# usb-geiger.net
KiCad netlist of a schematic drawn in EAGLE
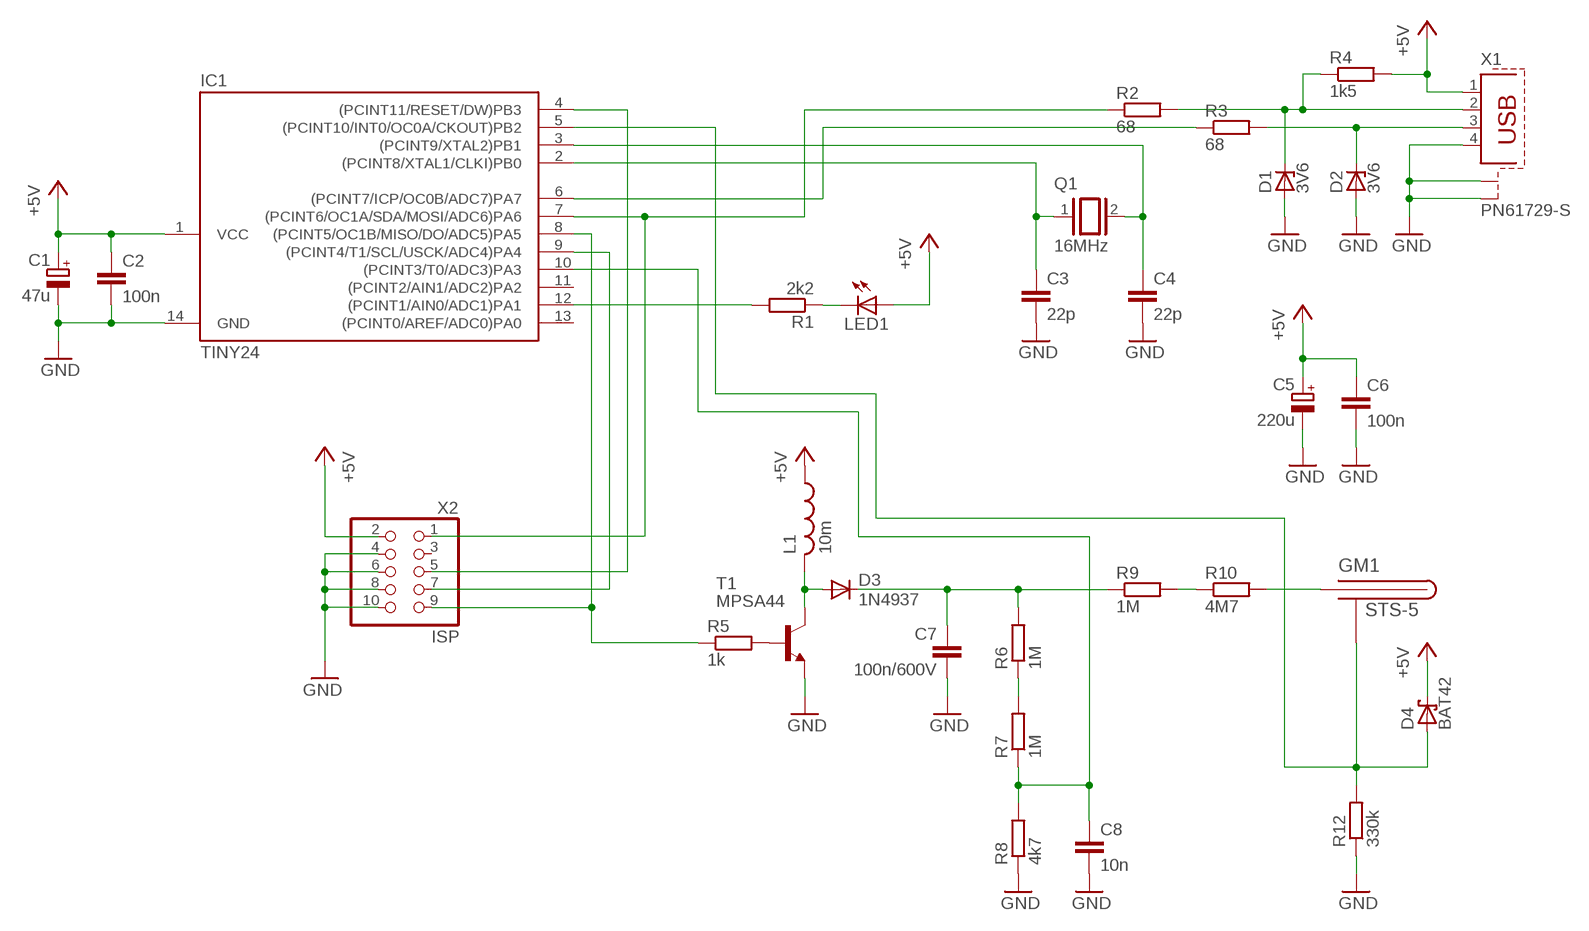
[diagram p0: schematic, sheet 1]

(export (version "E")
  (design (tool "Eeschema 10.0.6"))
  (components
    (comp (ref "C1")
      (value "47u")
      (footprint "eagle-import:E2,5-6")
      (libsource (lib "eagle-import") (part "CPOL-EUE2.5-6"))
    )
    (comp (ref "C2")
      (value "100n")
      (footprint "eagle-import:C050-025X075")
      (libsource (lib "eagle-import") (part "C-EU050-025X075"))
    )
    (comp (ref "C3")
      (value "22p")
      (footprint "eagle-import:C025-025X050")
      (libsource (lib "eagle-import") (part "C-EU025-025X050"))
    )
    (comp (ref "C4")
      (value "22p")
      (footprint "eagle-import:C025-025X050")
      (libsource (lib "eagle-import") (part "C-EU025-025X050"))
    )
    (comp (ref "C5")
      (value "220u")
      (footprint "eagle-import:E5-10,5")
      (libsource (lib "eagle-import") (part "CPOL-EUE5-10.5"))
    )
    (comp (ref "C6")
      (value "100n")
      (footprint "eagle-import:C050-025X075")
      (libsource (lib "eagle-import") (part "C-EU050-025X075"))
    )
    (comp (ref "C7")
      (value "100n/600V")
      (footprint "eagle-import:C225-113X268")
      (libsource (lib "eagle-import") (part "C-EU225-113X268"))
    )
    (comp (ref "C8")
      (value "10n")
      (footprint "eagle-import:C050-025X075")
      (libsource (lib "eagle-import") (part "C-EU050-025X075"))
    )
    (comp (ref "D1")
      (value "3V6")
      (footprint "eagle-import:DO34Z7")
      (libsource (lib "eagle-import") (part "ZENER-DIODEDO34-7"))
    )
    (comp (ref "D2")
      (value "3V6")
      (footprint "eagle-import:DO34Z7")
      (libsource (lib "eagle-import") (part "ZENER-DIODEDO34-7"))
    )
    (comp (ref "D3")
      (value "1N4937")
      (footprint "eagle-import:DO41-10")
      (libsource (lib "eagle-import") (part "1N4933"))
    )
    (comp (ref "D4")
      (value "BAT42")
      (footprint "eagle-import:DO35-10")
      (libsource (lib "eagle-import") (part "BAT42"))
    )
    (comp (ref "GM1")
      (value "STS-5")
      (footprint "eagle-import:STS-5")
      (libsource (lib "eagle-import") (part "STS-5"))
    )
    (comp (ref "IC1")
      (value "TINY24")
      (footprint "eagle-import:DIL14")
      (libsource (lib "eagle-import") (part "TINY24/44/84-PU"))
    )
    (comp (ref "L1")
      (value "10m")
      (footprint "eagle-import:0207_5V")
      (libsource (lib "eagle-import") (part "L-US0207/5V"))
    )
    (comp (ref "LED1")
      (value "LED3MM")
      (footprint "eagle-import:LED3MM")
      (libsource (lib "eagle-import") (part "LED3MM"))
    )
    (comp (ref "Q1")
      (value "16MHz")
      (footprint "eagle-import:QS")
      (libsource (lib "eagle-import") (part "XTAL/S"))
    )
    (comp (ref "R1")
      (value "2k2")
      (footprint "eagle-import:0207_10")
      (libsource (lib "eagle-import") (part "R-EU_0207/10"))
    )
    (comp (ref "R2")
      (value "68")
      (footprint "eagle-import:0207_10")
      (libsource (lib "eagle-import") (part "R-EU_0207/10"))
    )
    (comp (ref "R3")
      (value "68")
      (footprint "eagle-import:0207_10")
      (libsource (lib "eagle-import") (part "R-EU_0207/10"))
    )
    (comp (ref "R4")
      (value "1k5")
      (footprint "eagle-import:0207_10")
      (libsource (lib "eagle-import") (part "R-EU_0207/10"))
    )
    (comp (ref "R5")
      (value "1k")
      (footprint "eagle-import:0207_10")
      (libsource (lib "eagle-import") (part "R-EU_0207/10"))
    )
    (comp (ref "R6")
      (value "1M")
      (footprint "eagle-import:0207_10")
      (libsource (lib "eagle-import") (part "R-EU_0207/10"))
    )
    (comp (ref "R7")
      (value "1M")
      (footprint "eagle-import:0207_10")
      (libsource (lib "eagle-import") (part "R-EU_0207/10"))
    )
    (comp (ref "R8")
      (value "4k7")
      (footprint "eagle-import:0207_10")
      (libsource (lib "eagle-import") (part "R-EU_0207/10"))
    )
    (comp (ref "R9")
      (value "1M")
      (footprint "eagle-import:0207_10")
      (libsource (lib "eagle-import") (part "R-EU_0207/10"))
    )
    (comp (ref "R10")
      (value "4M7")
      (footprint "eagle-import:0207_10")
      (libsource (lib "eagle-import") (part "R-EU_0207/10"))
    )
    (comp (ref "R12")
      (value "330k")
      (footprint "eagle-import:0207_10")
      (libsource (lib "eagle-import") (part "R-EU_0207/10"))
    )
    (comp (ref "T1")
      (value "MPSA44")
      (footprint "eagle-import:TO92-EBC")
      (libsource (lib "eagle-import") (part "MPSA44"))
    )
    (comp (ref "X1")
      (value "PN61729-S")
      (footprint "eagle-import:PN61729-S")
      (libsource (lib "eagle-import") (part "PN61729-S"))
    )
    (comp (ref "X2")
      (value "PINHD-2X5")
      (footprint "eagle-import:2X05")
      (libsource (lib "eagle-import") (part "PINHD-2X5"))
    )
  )
  (nets
    (net (code "1") (name "+5V") (class "Default")
      (node (ref "C1") (pin "+") (pinfunction "+_+") (pintype "passive"))
      (node (ref "C2") (pin "1") (pinfunction "1_1") (pintype "passive"))
      (node (ref "C5") (pin "+") (pinfunction "+_+") (pintype "passive"))
      (node (ref "C6") (pin "1") (pinfunction "1_1") (pintype "passive"))
      (node (ref "D4") (pin "C") (pinfunction "C_C") (pintype "passive"))
      (node (ref "IC1") (pin "1") (pinfunction "VCC_1") (pintype "power_in"))
      (node (ref "L1") (pin "1") (pinfunction "1_1") (pintype "passive"))
      (node (ref "LED1") (pin "A") (pinfunction "A_A") (pintype "passive"))
      (node (ref "R4") (pin "2") (pinfunction "2_2") (pintype "passive"))
      (node (ref "X1") (pin "1") (pinfunction "1_1") (pintype "passive"))
      (node (ref "X2") (pin "2") (pinfunction "2_2") (pintype "passive"))
    )
    (net (code "2") (name "GND") (class "Default")
      (node (ref "C1") (pin "-") (pinfunction "-_-") (pintype "passive"))
      (node (ref "C2") (pin "2") (pinfunction "2_2") (pintype "passive"))
      (node (ref "C3") (pin "2") (pinfunction "2_2") (pintype "passive"))
      (node (ref "C4") (pin "2") (pinfunction "2_2") (pintype "passive"))
      (node (ref "C5") (pin "-") (pinfunction "-_-") (pintype "passive"))
      (node (ref "C6") (pin "2") (pinfunction "2_2") (pintype "passive"))
      (node (ref "C7") (pin "2") (pinfunction "2_2") (pintype "passive"))
      (node (ref "C8") (pin "2") (pinfunction "2_2") (pintype "passive"))
      (node (ref "D1") (pin "A") (pinfunction "A_A") (pintype "passive"))
      (node (ref "D2") (pin "A") (pinfunction "A_A") (pintype "passive"))
      (node (ref "IC1") (pin "14") (pinfunction "GND_14") (pintype "power_in"))
      (node (ref "R12") (pin "1") (pinfunction "1_1") (pintype "passive"))
      (node (ref "R8") (pin "1") (pinfunction "1_1") (pintype "passive"))
      (node (ref "T1") (pin "E") (pinfunction "E_E") (pintype "passive"))
      (node (ref "X1") (pin "4") (pinfunction "4_4") (pintype "passive"))
      (node (ref "X1") (pin "S1") (pinfunction "S1_S1") (pintype "passive"))
      (node (ref "X1") (pin "S2") (pinfunction "S2_S2") (pintype "passive"))
      (node (ref "X2") (pin "10") (pinfunction "10_10") (pintype "passive"))
      (node (ref "X2") (pin "4") (pinfunction "4_4") (pintype "passive"))
      (node (ref "X2") (pin "6") (pinfunction "6_6") (pintype "passive"))
      (node (ref "X2") (pin "8") (pinfunction "8_8") (pintype "passive"))
    )
    (net (code "3") (name "Net-(C7-Pad1)") (class "Default")
      (node (ref "C7") (pin "1") (pinfunction "1_1") (pintype "passive"))
      (node (ref "D3") (pin "C") (pinfunction "C_C") (pintype "passive"))
      (node (ref "R6") (pin "2") (pinfunction "2_2") (pintype "passive"))
      (node (ref "R9") (pin "1") (pinfunction "1_1") (pintype "passive"))
    )
    (net (code "4") (name "Net-(D1-PadC)") (class "Default")
      (node (ref "D1") (pin "C") (pinfunction "C_C") (pintype "passive"))
      (node (ref "R2") (pin "2") (pinfunction "2_2") (pintype "passive"))
      (node (ref "R4") (pin "1") (pinfunction "1_1") (pintype "passive"))
      (node (ref "X1") (pin "2") (pinfunction "2_2") (pintype "passive"))
    )
    (net (code "5") (name "Net-(D2-PadC)") (class "Default")
      (node (ref "D2") (pin "C") (pinfunction "C_C") (pintype "passive"))
      (node (ref "R3") (pin "2") (pinfunction "2_2") (pintype "passive"))
      (node (ref "X1") (pin "3") (pinfunction "3_3") (pintype "passive"))
    )
    (net (code "6") (name "Net-(D3-PadA)") (class "Default")
      (node (ref "D3") (pin "A") (pinfunction "A_A") (pintype "passive"))
      (node (ref "L1") (pin "2") (pinfunction "2_2") (pintype "passive"))
      (node (ref "T1") (pin "C") (pinfunction "C_C") (pintype "passive"))
    )
    (net (code "7") (name "Net-(GM1-PLUS-PadPLUS1)") (class "Default")
      (node (ref "GM1") (pin "PLUS1") (pinfunction "PLUS_PLUS1") (pintype "passive"))
      (node (ref "GM1") (pin "PLUS2") (pinfunction "PLUS_PLUS2") (pintype "passive"))
      (node (ref "R10") (pin "2") (pinfunction "2_2") (pintype "passive"))
    )
    (net (code "8") (name "Net-(IC1-(PCINT1{slash}AIN0{slash}ADC1)PA1)") (class "Default")
      (node (ref "IC1") (pin "12") (pinfunction "(PCINT1/AIN0/ADC1)PA1_12") (pintype "bidirectional"))
      (node (ref "R1") (pin "2") (pinfunction "2_2") (pintype "passive"))
    )
    (net (code "9") (name "Net-(IC1-(PCINT3{slash}T0{slash}ADC3)PA3)") (class "Default")
      (node (ref "C8") (pin "1") (pinfunction "1_1") (pintype "passive"))
      (node (ref "IC1") (pin "10") (pinfunction "(PCINT3/T0/ADC3)PA3_10") (pintype "bidirectional"))
      (node (ref "R7") (pin "1") (pinfunction "1_1") (pintype "passive"))
      (node (ref "R8") (pin "2") (pinfunction "2_2") (pintype "passive"))
    )
    (net (code "10") (name "Net-(IC1-(PCINT4{slash}T1{slash}SCL{slash}USCK{slash}ADC4)PA4)") (class "Default")
      (node (ref "IC1") (pin "9") (pinfunction "(PCINT4/T1/SCL/USCK/ADC4)PA4_9") (pintype "bidirectional"))
      (node (ref "X2") (pin "7") (pinfunction "7_7") (pintype "passive"))
    )
    (net (code "11") (name "Net-(IC1-(PCINT5{slash}OC1B{slash}MISO{slash}DO{slash}ADC5)PA5)") (class "Default")
      (node (ref "IC1") (pin "8") (pinfunction "(PCINT5/OC1B/MISO/DO/ADC5)PA5_8") (pintype "bidirectional"))
      (node (ref "R5") (pin "1") (pinfunction "1_1") (pintype "passive"))
      (node (ref "X2") (pin "9") (pinfunction "9_9") (pintype "passive"))
    )
    (net (code "12") (name "Net-(IC1-(PCINT6{slash}OC1A{slash}SDA{slash}MOSI{slash}ADC6)PA6)") (class "Default")
      (node (ref "IC1") (pin "7") (pinfunction "(PCINT6/OC1A/SDA/MOSI/ADC6)PA6_7") (pintype "bidirectional"))
      (node (ref "R2") (pin "1") (pinfunction "1_1") (pintype "passive"))
      (node (ref "X2") (pin "1") (pinfunction "1_1") (pintype "passive"))
    )
    (net (code "13") (name "Net-(IC1-(PCINT7{slash}ICP{slash}OC0B{slash}ADC7)PA7)") (class "Default")
      (node (ref "IC1") (pin "6") (pinfunction "(PCINT7/ICP/OC0B/ADC7)PA7_6") (pintype "bidirectional"))
      (node (ref "R3") (pin "1") (pinfunction "1_1") (pintype "passive"))
    )
    (net (code "14") (name "Net-(IC1-(PCINT8{slash}XTAL1{slash}CLKI)PB0)") (class "Default")
      (node (ref "C3") (pin "1") (pinfunction "1_1") (pintype "passive"))
      (node (ref "IC1") (pin "2") (pinfunction "(PCINT8/XTAL1/CLKI)PB0_2") (pintype "bidirectional"))
      (node (ref "Q1") (pin "1") (pinfunction "1_1") (pintype "passive"))
    )
    (net (code "15") (name "Net-(IC1-(PCINT9{slash}XTAL2)PB1)") (class "Default")
      (node (ref "C4") (pin "1") (pinfunction "1_1") (pintype "passive"))
      (node (ref "IC1") (pin "3") (pinfunction "(PCINT9/XTAL2)PB1_3") (pintype "bidirectional"))
      (node (ref "Q1") (pin "2") (pinfunction "2_2") (pintype "passive"))
    )
    (net (code "16") (name "Net-(IC1-(PCINT10{slash}INT0{slash}OC0A{slash}CKOUT)PB2)") (class "Default")
      (node (ref "D4") (pin "A") (pinfunction "A_A") (pintype "passive"))
      (node (ref "GM1") (pin "MINUS1") (pinfunction "MINUS_MINUS1") (pintype "passive"))
      (node (ref "GM1") (pin "MINUS2") (pinfunction "MINUS_MINUS2") (pintype "passive"))
      (node (ref "IC1") (pin "5") (pinfunction "(PCINT10/INT0/OC0A/CKOUT)PB2_5") (pintype "bidirectional"))
      (node (ref "R12") (pin "2") (pinfunction "2_2") (pintype "passive"))
    )
    (net (code "17") (name "Net-(IC1-(PCINT11{slash}RESET{slash}DW)PB3)") (class "Default")
      (node (ref "IC1") (pin "4") (pinfunction "(PCINT11/RESET/DW)PB3_4") (pintype "bidirectional"))
      (node (ref "X2") (pin "5") (pinfunction "5_5") (pintype "passive"))
    )
    (net (code "18") (name "Net-(LED1-C)") (class "Default")
      (node (ref "LED1") (pin "K") (pinfunction "C_K") (pintype "passive"))
      (node (ref "R1") (pin "1") (pinfunction "1_1") (pintype "passive"))
    )
    (net (code "19") (name "Net-(R5-Pad2)") (class "Default")
      (node (ref "R5") (pin "2") (pinfunction "2_2") (pintype "passive"))
      (node (ref "T1") (pin "B") (pinfunction "B_B") (pintype "passive"))
    )
    (net (code "20") (name "Net-(R6-Pad1)") (class "Default")
      (node (ref "R6") (pin "1") (pinfunction "1_1") (pintype "passive"))
      (node (ref "R7") (pin "2") (pinfunction "2_2") (pintype "passive"))
    )
    (net (code "21") (name "Net-(R10-Pad1)") (class "Default")
      (node (ref "R10") (pin "1") (pinfunction "1_1") (pintype "passive"))
      (node (ref "R9") (pin "2") (pinfunction "2_2") (pintype "passive"))
    )
    (net (code "22") (name "unconnected-(IC1-(PCINT0{slash}AREF{slash}ADC0)PA0-Pad13)") (class "Default")
      (node (ref "IC1") (pin "13") (pinfunction "(PCINT0/AREF/ADC0)PA0_13") (pintype "bidirectional"))
    )
    (net (code "23") (name "unconnected-(IC1-(PCINT2{slash}AIN1{slash}ADC2)PA2-Pad11)") (class "Default")
      (node (ref "IC1") (pin "11") (pinfunction "(PCINT2/AIN1/ADC2)PA2_11") (pintype "bidirectional"))
    )
    (net (code "24") (name "unconnected-(X2-Pad3)") (class "Default")
      (node (ref "X2") (pin "3") (pinfunction "3_3") (pintype "passive"))
    )
  )
)
